# Pr_tica-01.net
KiCad netlist of a schematic drawn in EasyEDA
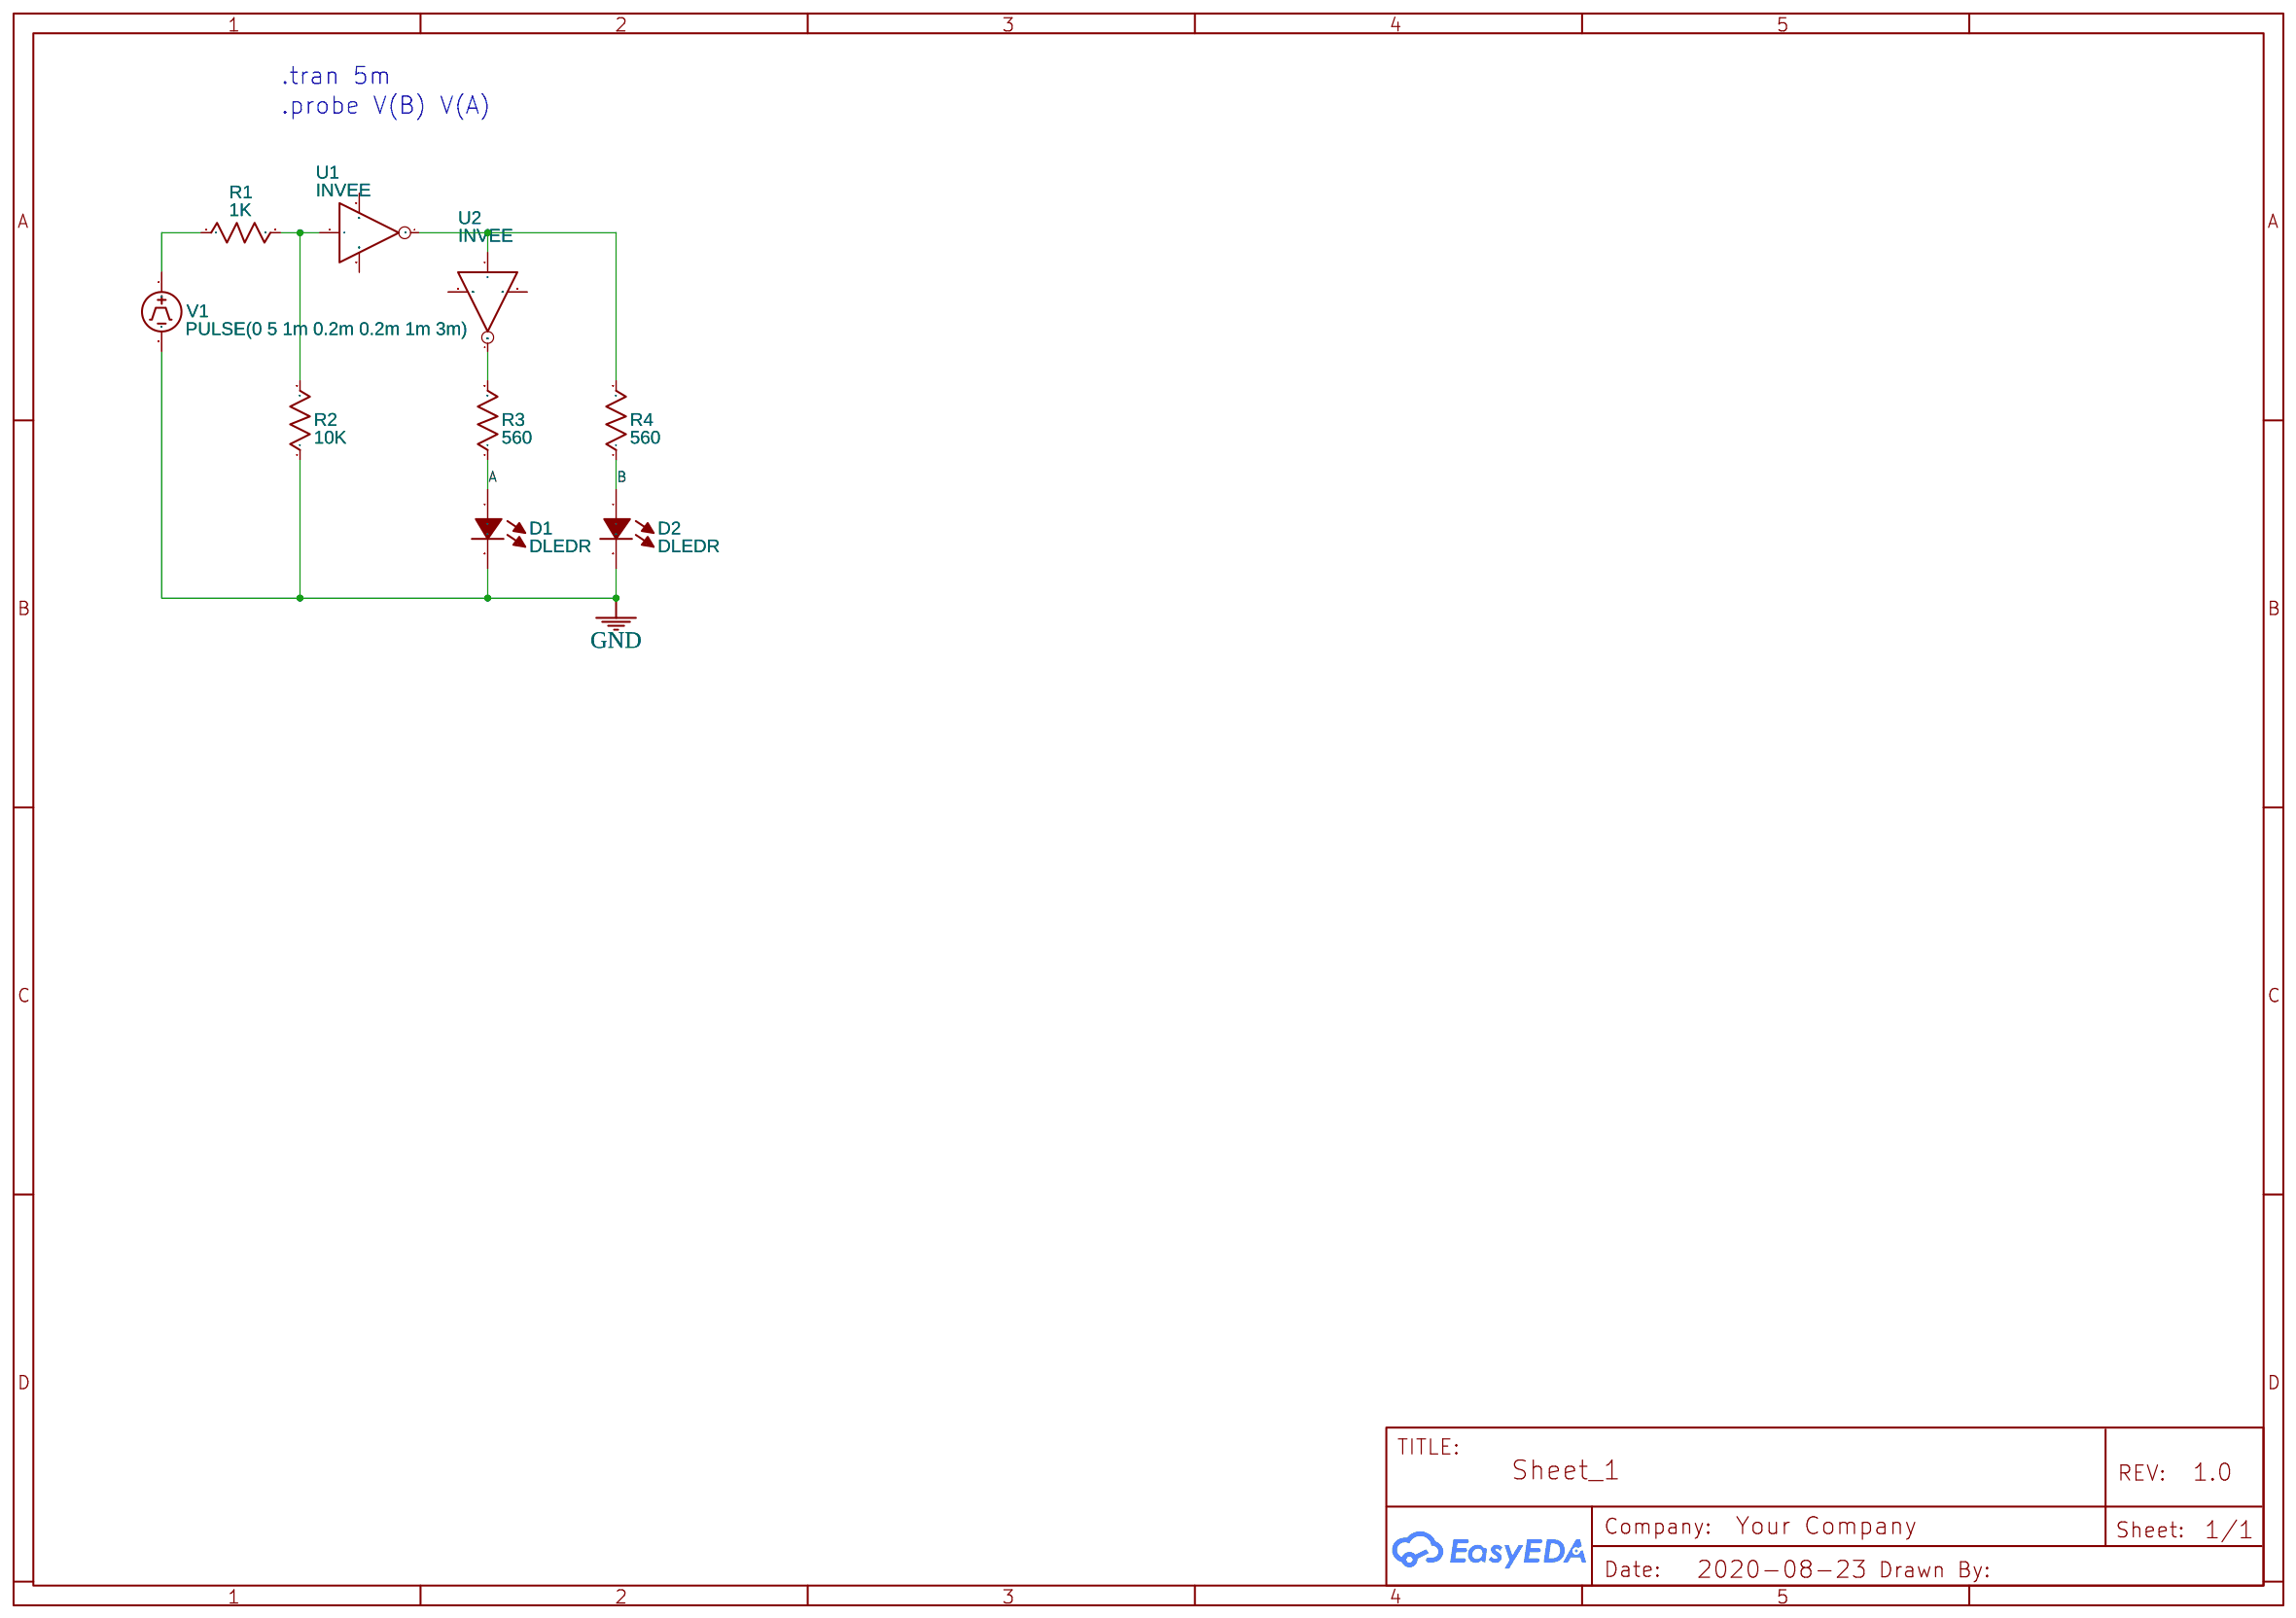
[diagram p0: schematic sheet]

(export (version "E")
  (design (tool "Eeschema 10.0.6"))
  (components
    (comp (ref "D1") (value "DLEDR") (libsource (lib "") (part "DLEDR")))
    (comp (ref "D2") (value "DLEDR") (libsource (lib "") (part "DLEDR")))
    (comp (ref "R1") (value "1K") (libsource (lib "") (part "Resistor_US_1")))
    (comp (ref "R2") (value "10K") (libsource (lib "") (part "Resistor_US")))
    (comp (ref "R3") (value "560") (libsource (lib "") (part "Resistor_US")))
    (comp (ref "R4") (value "560") (libsource (lib "") (part "Resistor_US")))
    (comp (ref "U1") (value "INVEE") (libsource (lib "") (part "LOGIC")))
    (comp (ref "U2") (value "INVEE") (libsource (lib "") (part "LOGIC_1")))
    (comp (ref "V1") (value "PULSE(0 5 1m 0.2m 0.2m 1m 3m)") (libsource (lib "") (part "VPULSE")))
  )
  (nets
    (net (code "1") (name "/A") (class "Default")
      (node (ref "D1") (pin "1") (pinfunction "A_1") (pintype "unspecified"))
      (node (ref "R3") (pin "1") (pinfunction "1_1") (pintype "unspecified"))
    )
    (net (code "2") (name "/B") (class "Default")
      (node (ref "D2") (pin "1") (pinfunction "A_1") (pintype "unspecified"))
      (node (ref "R4") (pin "1") (pinfunction "1_1") (pintype "unspecified"))
    )
    (net (code "3") (name "GND") (class "Default")
      (node (ref "D1") (pin "2") (pinfunction "C_2") (pintype "unspecified"))
      (node (ref "D2") (pin "2") (pinfunction "C_2") (pintype "unspecified"))
      (node (ref "R2") (pin "1") (pinfunction "1_1") (pintype "unspecified"))
      (node (ref "V1") (pin "2") (pinfunction "2_2") (pintype "unspecified"))
    )
    (net (code "4") (name "Net-(R1-Pad1)") (class "Default")
      (node (ref "R1") (pin "1") (pinfunction "1_1") (pintype "unspecified"))
      (node (ref "V1") (pin "1") (pinfunction "1_1") (pintype "unspecified"))
    )
    (net (code "5") (name "Net-(U1-IN)") (class "Default")
      (node (ref "R1") (pin "2") (pinfunction "2_2") (pintype "unspecified"))
      (node (ref "R2") (pin "2") (pinfunction "2_2") (pintype "unspecified"))
      (node (ref "U1") (pin "1") (pinfunction "IN_1") (pintype "input"))
    )
    (net (code "6") (name "Net-(U1-OUT)") (class "Default")
      (node (ref "R4") (pin "2") (pinfunction "2_2") (pintype "unspecified"))
      (node (ref "U1") (pin "4") (pinfunction "OUT_4") (pintype "output"))
      (node (ref "U2") (pin "1") (pinfunction "IN_1") (pintype "input"))
    )
    (net (code "7") (name "Net-(U2-OUT)") (class "Default")
      (node (ref "R3") (pin "2") (pinfunction "2_2") (pintype "unspecified"))
      (node (ref "U2") (pin "4") (pinfunction "OUT_4") (pintype "output"))
    )
    (net (code "8") (name "unconnected-(U1-GND-Pad3)") (class "Default")
      (node (ref "U1") (pin "3") (pinfunction "GND_3") (pintype "passive"))
    )
    (net (code "9") (name "unconnected-(U1-VDD-Pad2)") (class "Default")
      (node (ref "U1") (pin "2") (pinfunction "VDD_2") (pintype "passive"))
    )
    (net (code "10") (name "unconnected-(U2-GND-Pad3)") (class "Default")
      (node (ref "U2") (pin "3") (pinfunction "GND_3") (pintype "passive"))
    )
    (net (code "11") (name "unconnected-(U2-VDD-Pad2)") (class "Default")
      (node (ref "U2") (pin "2") (pinfunction "VDD_2") (pintype "passive"))
    )
  )
)
